# FlightComputer_DeploymentBoard.net
KiCad netlist of a schematic drawn in EAGLE
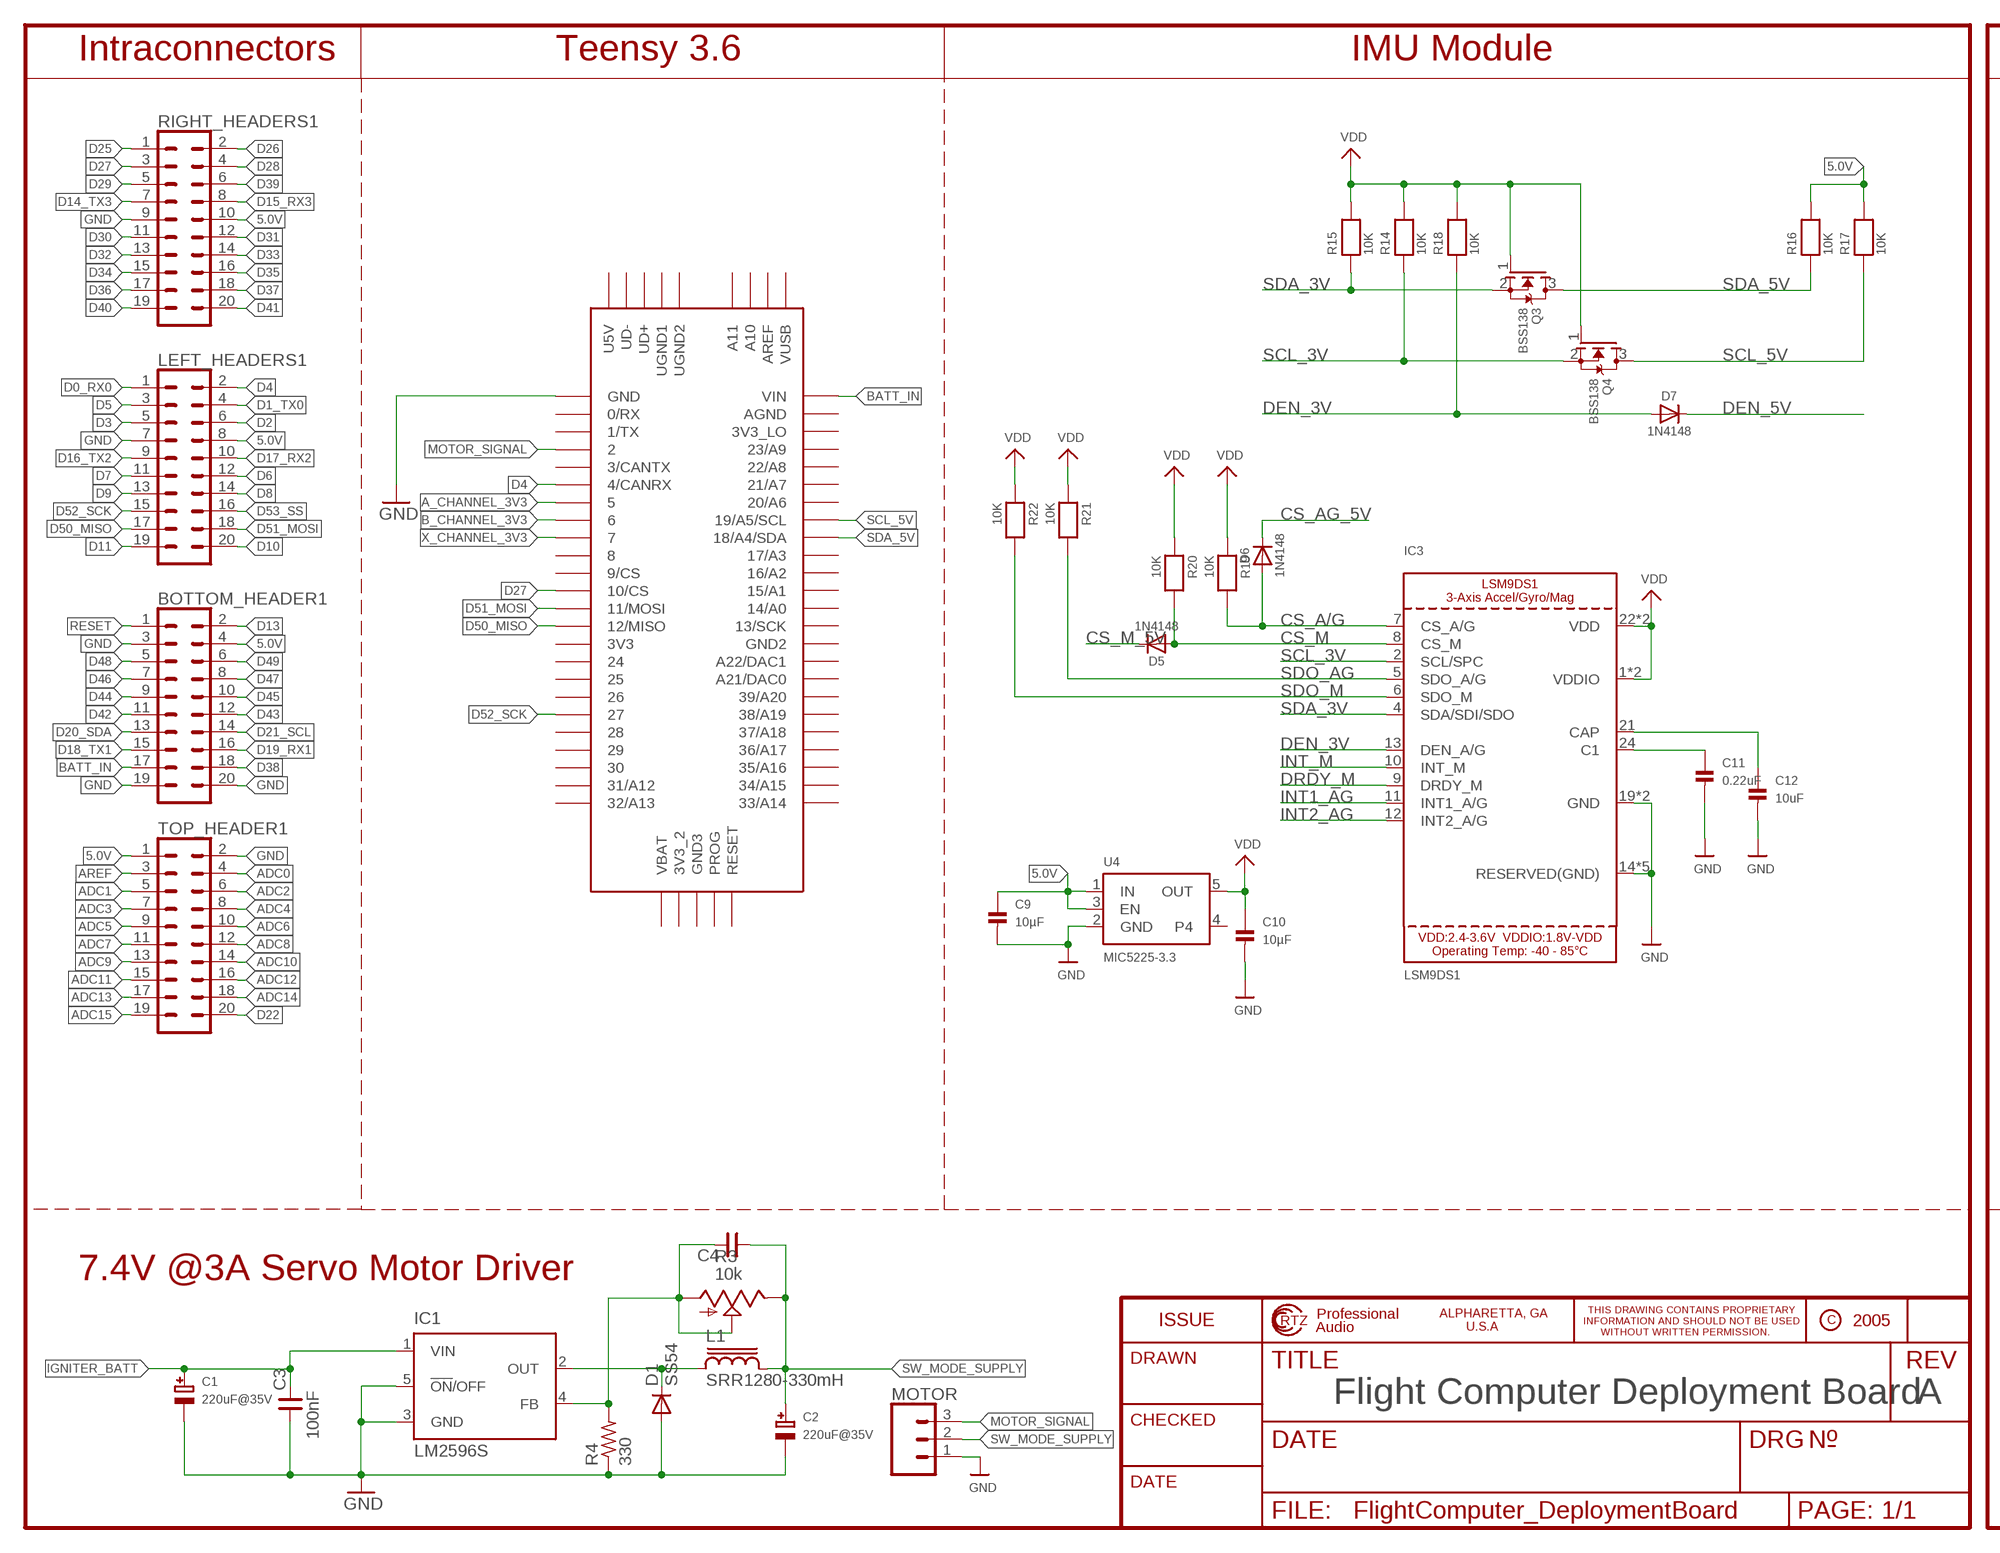
[diagram p0: schematic, sheet 1, part 1 of 2]
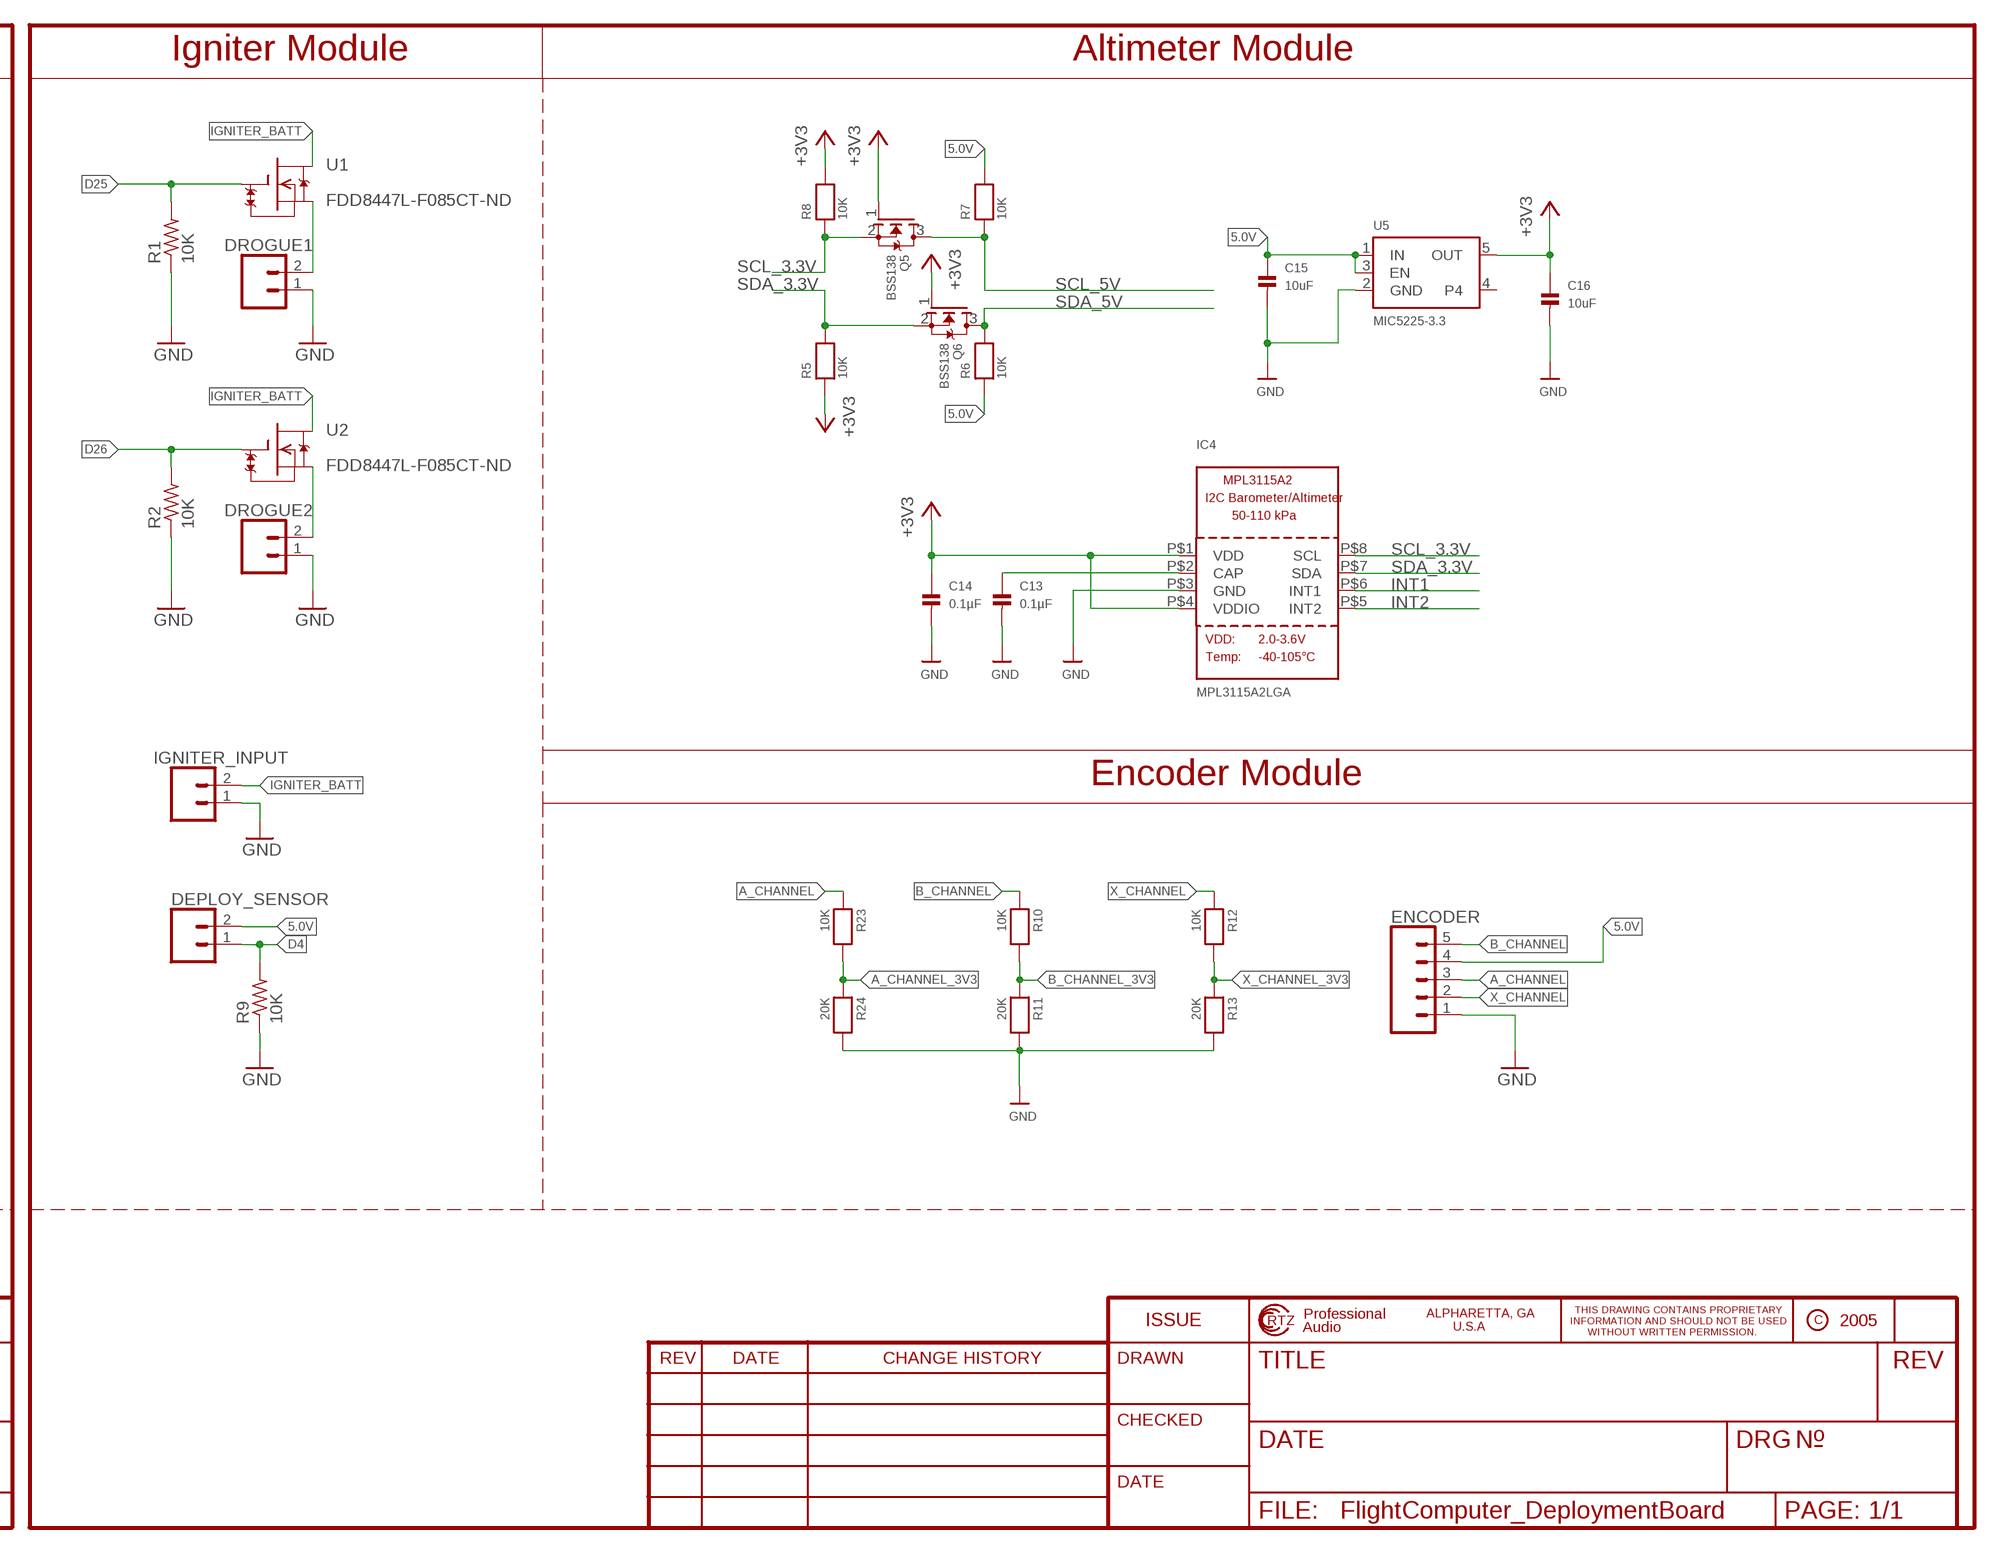
[diagram p1: schematic, sheet 1, part 2 of 2]

(export (version "E")
  (design (tool "Eeschema 10.0.6"))
  (components
    (comp (ref "BOTTOM_HEADER1")
      (value "CONN_10X2")
      (footprint "eagle-import:2X10")
      (libsource (lib "eagle-import") (part "CONN_10X2"))
    )
    (comp (ref "C1")
      (value "220uF@35V")
      (footprint "eagle-import:PANASONIC_D")
      (libsource (lib "eagle-import") (part "CAP_ELECTROLYTICPANASONIC_D"))
    )
    (comp (ref "C2")
      (value "220uF@35V")
      (footprint "eagle-import:PANASONIC_D")
      (libsource (lib "eagle-import") (part "CAP_ELECTROLYTICPANASONIC_D"))
    )
    (comp (ref "C3")
      (value "100nF")
      (footprint "eagle-import:0603")
      (libsource (lib "eagle-import") (part "CNP-0603"))
    )
    (comp (ref "C4")
      (value "CNP-0603")
      (footprint "eagle-import:0603")
      (libsource (lib "eagle-import") (part "CNP-0603"))
    )
    (comp (ref "C9")
      (value "10µF")
      (footprint "eagle-import:0603")
      (libsource (lib "eagle-import") (part "CAP_CERAMIC0603"))
    )
    (comp (ref "C10")
      (value "10µF")
      (footprint "eagle-import:0603")
      (libsource (lib "eagle-import") (part "CAP_CERAMIC0603"))
    )
    (comp (ref "C11")
      (value "0.22uF")
      (footprint "eagle-import:0603")
      (libsource (lib "eagle-import") (part "CAP_CERAMIC0603"))
    )
    (comp (ref "C12")
      (value "10uF")
      (footprint "eagle-import:0603")
      (libsource (lib "eagle-import") (part "CAP_CERAMIC0603"))
    )
    (comp (ref "C13")
      (value "0.1µF")
      (footprint "eagle-import:0603")
      (libsource (lib "eagle-import") (part "CAP_CERAMIC0603"))
    )
    (comp (ref "C14")
      (value "0.1µF")
      (footprint "eagle-import:0603")
      (libsource (lib "eagle-import") (part "CAP_CERAMIC0603"))
    )
    (comp (ref "C15")
      (value "10uF")
      (footprint "eagle-import:0603")
      (libsource (lib "eagle-import") (part "CAP_CERAMIC0603"))
    )
    (comp (ref "C16")
      (value "10uF")
      (footprint "eagle-import:0603")
      (libsource (lib "eagle-import") (part "CAP_CERAMIC0603"))
    )
    (comp (ref "D1")
      (value "SS54")
      (footprint "eagle-import:DO214AB")
      (fields (field (name "MF") "Fairchild") (field (name "MPN") "S3G"))
      (libsource (lib "eagle-import") (part "S3G"))
    )
    (comp (ref "D5")
      (value "1N4148")
      (footprint "eagle-import:SOD-323")
      (libsource (lib "eagle-import") (part "DIODESOD-323"))
    )
    (comp (ref "D6")
      (value "1N4148")
      (footprint "eagle-import:SOD-323")
      (libsource (lib "eagle-import") (part "DIODESOD-323"))
    )
    (comp (ref "D7")
      (value "1N4148")
      (footprint "eagle-import:SOD-323")
      (libsource (lib "eagle-import") (part "DIODESOD-323"))
    )
    (comp (ref "DEPLOY_SENSOR")
      (value "CONN_023.5MM")
      (footprint "eagle-import:SCREWTERMINAL-3.5MM-2")
      (libsource (lib "eagle-import") (part "CONN_023.5MM"))
    )
    (comp (ref "DROGUE1")
      (value "CONN_023.5MM")
      (footprint "eagle-import:SCREWTERMINAL-3.5MM-2")
      (libsource (lib "eagle-import") (part "CONN_023.5MM"))
    )
    (comp (ref "DROGUE2")
      (value "CONN_023.5MM")
      (footprint "eagle-import:SCREWTERMINAL-3.5MM-2")
      (libsource (lib "eagle-import") (part "CONN_023.5MM"))
    )
    (comp (ref "ENCODER")
      (value "CONN_05")
      (footprint "eagle-import:1X05")
      (libsource (lib "eagle-import") (part "CONN_05"))
    )
    (comp (ref "IC1")
      (value "LM2596S")
      (footprint "eagle-import:TO263-5")
      (fields (field (name "MF") "NATIONAL SEMICONDUCTOR") (field (name "MPN") "LM2596S-ADJ/NOPB"))
      (libsource (lib "eagle-import") (part "LM2596S"))
    )
    (comp (ref "IC3")
      (value "LSM9DS1")
      (footprint "eagle-import:LGA24_3.5X3.1MM")
      (libsource (lib "eagle-import") (part "LSM9DS1"))
    )
    (comp (ref "IC4")
      (value "MPL3115A2LGA")
      (footprint "eagle-import:LGA8")
      (libsource (lib "eagle-import") (part "MPL3115A2LGA"))
    )
    (comp (ref "IGNITER_INPUT")
      (value "CONN_02")
      (footprint "eagle-import:1X02")
      (libsource (lib "eagle-import") (part "CONN_02"))
    )
    (comp (ref "L1")
      (value "SRR1280-330mH")
      (footprint "eagle-import:SRR1280")
      (libsource (lib "eagle-import") (part "SRR1280"))
    )
    (comp (ref "LEFT_HEADERS1")
      (value "CONN_10X2")
      (footprint "eagle-import:2X10")
      (libsource (lib "eagle-import") (part "CONN_10X2"))
    )
    (comp (ref "MOTOR")
      (value "CONN_03")
      (footprint "eagle-import:1X03")
      (libsource (lib "eagle-import") (part "CONN_03"))
    )
    (comp (ref "Q3")
      (value "BSS138")
      (footprint "eagle-import:SOT23-WIDE")
      (libsource (lib "eagle-import") (part "MOSFET-NWIDE"))
    )
    (comp (ref "Q4")
      (value "BSS138")
      (footprint "eagle-import:SOT23-WIDE")
      (libsource (lib "eagle-import") (part "MOSFET-NWIDE"))
    )
    (comp (ref "Q5")
      (value "BSS138")
      (footprint "eagle-import:SOT23-WIDE")
      (libsource (lib "eagle-import") (part "MOSFET-NWIDE"))
    )
    (comp (ref "Q6")
      (value "BSS138")
      (footprint "eagle-import:SOT23-WIDE")
      (libsource (lib "eagle-import") (part "MOSFET-NWIDE"))
    )
    (comp (ref "R1")
      (value "10K")
      (footprint "eagle-import:R0805")
      (libsource (lib "eagle-import") (part "R-US_R0805"))
    )
    (comp (ref "R2")
      (value "10K")
      (footprint "eagle-import:R0805")
      (libsource (lib "eagle-import") (part "R-US_R0805"))
    )
    (comp (ref "R3")
      (value "10k")
      (footprint "eagle-import:S64W")
      (libsource (lib "eagle-import") (part "TRIM_US-S64W"))
    )
    (comp (ref "R4")
      (value "330")
      (footprint "eagle-import:R0603")
      (libsource (lib "eagle-import") (part "R-US_R0603"))
    )
    (comp (ref "R5")
      (value "10K")
      (footprint "eagle-import:0603")
      (libsource (lib "eagle-import") (part "RESISTOR0603"))
    )
    (comp (ref "R6")
      (value "10K")
      (footprint "eagle-import:0603")
      (libsource (lib "eagle-import") (part "RESISTOR0603"))
    )
    (comp (ref "R7")
      (value "10K")
      (footprint "eagle-import:0603")
      (libsource (lib "eagle-import") (part "RESISTOR0603"))
    )
    (comp (ref "R8")
      (value "10K")
      (footprint "eagle-import:0603")
      (libsource (lib "eagle-import") (part "RESISTOR0603"))
    )
    (comp (ref "R9")
      (value "10K")
      (footprint "eagle-import:R0805")
      (libsource (lib "eagle-import") (part "R-US_R0805"))
    )
    (comp (ref "R10")
      (value "10K")
      (footprint "eagle-import:0603")
      (libsource (lib "eagle-import") (part "RESISTOR0603"))
    )
    (comp (ref "R11")
      (value "20K")
      (footprint "eagle-import:0603")
      (libsource (lib "eagle-import") (part "RESISTOR0603"))
    )
    (comp (ref "R12")
      (value "10K")
      (footprint "eagle-import:0603")
      (libsource (lib "eagle-import") (part "RESISTOR0603"))
    )
    (comp (ref "R13")
      (value "20K")
      (footprint "eagle-import:0603")
      (libsource (lib "eagle-import") (part "RESISTOR0603"))
    )
    (comp (ref "R14")
      (value "10K")
      (footprint "eagle-import:0603")
      (libsource (lib "eagle-import") (part "RESISTOR0603"))
    )
    (comp (ref "R15")
      (value "10K")
      (footprint "eagle-import:0603")
      (libsource (lib "eagle-import") (part "RESISTOR0603"))
    )
    (comp (ref "R16")
      (value "10K")
      (footprint "eagle-import:0603")
      (libsource (lib "eagle-import") (part "RESISTOR0603"))
    )
    (comp (ref "R17")
      (value "10K")
      (footprint "eagle-import:0603")
      (libsource (lib "eagle-import") (part "RESISTOR0603"))
    )
    (comp (ref "R18")
      (value "10K")
      (footprint "eagle-import:0603")
      (libsource (lib "eagle-import") (part "RESISTOR0603"))
    )
    (comp (ref "R19")
      (value "10K")
      (footprint "eagle-import:0603")
      (libsource (lib "eagle-import") (part "RESISTOR0603"))
    )
    (comp (ref "R20")
      (value "10K")
      (footprint "eagle-import:0603")
      (libsource (lib "eagle-import") (part "RESISTOR0603"))
    )
    (comp (ref "R21")
      (value "10K")
      (footprint "eagle-import:0603")
      (libsource (lib "eagle-import") (part "RESISTOR0603"))
    )
    (comp (ref "R22")
      (value "10K")
      (footprint "eagle-import:0603")
      (libsource (lib "eagle-import") (part "RESISTOR0603"))
    )
    (comp (ref "R23")
      (value "10K")
      (footprint "eagle-import:0603")
      (libsource (lib "eagle-import") (part "RESISTOR0603"))
    )
    (comp (ref "R24")
      (value "20K")
      (footprint "eagle-import:0603")
      (libsource (lib "eagle-import") (part "RESISTOR0603"))
    )
    (comp (ref "RIGHT_HEADERS1")
      (value "CONN_10X2")
      (footprint "eagle-import:2X10")
      (libsource (lib "eagle-import") (part "CONN_10X2"))
    )
    (comp (ref "TOP_HEADER1")
      (value "CONN_10X2")
      (footprint "eagle-import:2X10")
      (libsource (lib "eagle-import") (part "CONN_10X2"))
    )
    (comp (ref "U$1")
      (value "TEENSY_3.5/3.6")
      (footprint "eagle-import:TEENSY_3.5_3.6")
      (libsource (lib "eagle-import") (part "TEENSY_3.5/3.6"))
    )
    (comp (ref "U1")
      (value "FDD8447L-F085CT-ND")
      (footprint "eagle-import:TO252")
      (libsource (lib "eagle-import") (part "TSM4ND50"))
    )
    (comp (ref "U2")
      (value "FDD8447L-F085CT-ND")
      (footprint "eagle-import:TO252")
      (libsource (lib "eagle-import") (part "TSM4ND50"))
    )
    (comp (ref "U4")
      (value "MIC5225-3.3")
      (footprint "eagle-import:SOT23-5")
      (libsource (lib "eagle-import") (part "VREG_SOT23-5"))
    )
    (comp (ref "U5")
      (value "MIC5225-3.3")
      (footprint "eagle-import:SOT23-5")
      (libsource (lib "eagle-import") (part "VREG_SOT23-5"))
    )
  )
  (nets
    (net (code "1") (name "+3V3") (class "Default")
      (node (ref "C14") (pin "1") (pinfunction "P$1_1") (pintype "passive"))
      (node (ref "C16") (pin "1") (pinfunction "P$1_1") (pintype "passive"))
      (node (ref "IC4") (pin "P$1") (pinfunction "VDD_P$1") (pintype "power_in"))
      (node (ref "IC4") (pin "P$4") (pinfunction "VDDIO_P$4") (pintype "power_in"))
      (node (ref "Q5") (pin "1") (pinfunction "G_1") (pintype "bidirectional"))
      (node (ref "Q6") (pin "1") (pinfunction "G_1") (pintype "bidirectional"))
      (node (ref "R5") (pin "1") (pinfunction "1_1") (pintype "passive"))
      (node (ref "R8") (pin "2") (pinfunction "2_2") (pintype "passive"))
      (node (ref "U5") (pin "5") (pinfunction "OUT_5") (pintype "power_in"))
    )
    (net (code "2") (name "/CS_AG_5V") (class "Default")
      (node (ref "D6") (pin "C") (pinfunction "C_C") (pintype "passive"))
    )
    (net (code "3") (name "/CS_A{slash}G") (class "Default")
      (node (ref "D6") (pin "A") (pinfunction "A_A") (pintype "passive"))
      (node (ref "IC3") (pin "7") (pinfunction "CS_A/G_7") (pintype "bidirectional"))
      (node (ref "R19") (pin "2") (pinfunction "2_2") (pintype "passive"))
    )
    (net (code "4") (name "/CS_M") (class "Default")
      (node (ref "D5") (pin "A") (pinfunction "A_A") (pintype "passive"))
      (node (ref "IC3") (pin "8") (pinfunction "CS_M_8") (pintype "bidirectional"))
      (node (ref "R20") (pin "2") (pinfunction "2_2") (pintype "passive"))
    )
    (net (code "5") (name "/CS_M_5V") (class "Default")
      (node (ref "D5") (pin "C") (pinfunction "C_C") (pintype "passive"))
    )
    (net (code "6") (name "/DEN_3V") (class "Default")
      (node (ref "D7") (pin "A") (pinfunction "A_A") (pintype "passive"))
      (node (ref "IC3") (pin "13") (pinfunction "DEN_A/G_13") (pintype "bidirectional"))
      (node (ref "R18") (pin "1") (pinfunction "1_1") (pintype "passive"))
    )
    (net (code "7") (name "/DEN_5V") (class "Default")
      (node (ref "D7") (pin "C") (pinfunction "C_C") (pintype "passive"))
    )
    (net (code "8") (name "/DRDY_M") (class "Default")
      (node (ref "IC3") (pin "9") (pinfunction "DRDY_M_9") (pintype "bidirectional"))
    )
    (net (code "9") (name "/INT1") (class "Default")
      (node (ref "IC4") (pin "P$6") (pinfunction "INT1_P$6") (pintype "output"))
    )
    (net (code "10") (name "/INT1_AG") (class "Default")
      (node (ref "IC3") (pin "11") (pinfunction "INT1_A/G_11") (pintype "bidirectional"))
    )
    (net (code "11") (name "/INT2") (class "Default")
      (node (ref "IC4") (pin "P$5") (pinfunction "INT2_P$5") (pintype "output"))
    )
    (net (code "12") (name "/INT2_AG") (class "Default")
      (node (ref "IC3") (pin "12") (pinfunction "INT2_A/G_12") (pintype "bidirectional"))
    )
    (net (code "13") (name "/INT_M") (class "Default")
      (node (ref "IC3") (pin "10") (pinfunction "INT_M_10") (pintype "bidirectional"))
    )
    (net (code "14") (name "/SCL_3.3V") (class "Default")
      (node (ref "IC4") (pin "P$8") (pinfunction "SCL_P$8") (pintype "bidirectional"))
      (node (ref "Q5") (pin "2") (pinfunction "S_2") (pintype "bidirectional"))
      (node (ref "R8") (pin "1") (pinfunction "1_1") (pintype "passive"))
    )
    (net (code "15") (name "/SCL_3V") (class "Default")
      (node (ref "IC3") (pin "2") (pinfunction "SCL/SPC_2") (pintype "bidirectional"))
      (node (ref "Q4") (pin "2") (pinfunction "S_2") (pintype "bidirectional"))
      (node (ref "R14") (pin "1") (pinfunction "1_1") (pintype "passive"))
    )
    (net (code "16") (name "/SDA_3.3V") (class "Default")
      (node (ref "IC4") (pin "P$7") (pinfunction "SDA_P$7") (pintype "bidirectional"))
      (node (ref "Q6") (pin "2") (pinfunction "S_2") (pintype "bidirectional"))
      (node (ref "R5") (pin "2") (pinfunction "2_2") (pintype "passive"))
    )
    (net (code "17") (name "/SDA_3V") (class "Default")
      (node (ref "IC3") (pin "4") (pinfunction "SDA/SDI/SDO_4") (pintype "bidirectional"))
      (node (ref "Q3") (pin "2") (pinfunction "S_2") (pintype "bidirectional"))
      (node (ref "R15") (pin "1") (pinfunction "1_1") (pintype "passive"))
    )
    (net (code "18") (name "/SDO_AG") (class "Default")
      (node (ref "IC3") (pin "5") (pinfunction "SDO_A/G_5") (pintype "bidirectional"))
      (node (ref "R21") (pin "2") (pinfunction "2_2") (pintype "passive"))
    )
    (net (code "19") (name "/SDO_M") (class "Default")
      (node (ref "IC3") (pin "6") (pinfunction "SDO_M_6") (pintype "bidirectional"))
      (node (ref "R22") (pin "2") (pinfunction "2_2") (pintype "passive"))
    )
    (net (code "20") (name "5.0V") (class "Default")
      (node (ref "BOTTOM_HEADER1") (pin "4") (pinfunction "4_4") (pintype "passive"))
      (node (ref "C15") (pin "1") (pinfunction "P$1_1") (pintype "passive"))
      (node (ref "C9") (pin "1") (pinfunction "P$1_1") (pintype "passive"))
      (node (ref "DEPLOY_SENSOR") (pin "2") (pinfunction "2_2") (pintype "passive"))
      (node (ref "ENCODER") (pin "4") (pinfunction "4_4") (pintype "passive"))
      (node (ref "LEFT_HEADERS1") (pin "8") (pinfunction "8_8") (pintype "passive"))
      (node (ref "R16") (pin "2") (pinfunction "2_2") (pintype "passive"))
      (node (ref "R17") (pin "2") (pinfunction "2_2") (pintype "passive"))
      (node (ref "R6") (pin "1") (pinfunction "1_1") (pintype "passive"))
      (node (ref "R7") (pin "2") (pinfunction "2_2") (pintype "passive"))
      (node (ref "RIGHT_HEADERS1") (pin "10") (pinfunction "10_10") (pintype "passive"))
      (node (ref "TOP_HEADER1") (pin "1") (pinfunction "1_1") (pintype "passive"))
      (node (ref "U4") (pin "1") (pinfunction "IN_1") (pintype "power_in"))
      (node (ref "U4") (pin "3") (pinfunction "EN_3") (pintype "input"))
      (node (ref "U5") (pin "1") (pinfunction "IN_1") (pintype "power_in"))
      (node (ref "U5") (pin "3") (pinfunction "EN_3") (pintype "input"))
    )
    (net (code "21") (name "ADC0") (class "Default")
      (node (ref "TOP_HEADER1") (pin "4") (pinfunction "4_4") (pintype "passive"))
    )
    (net (code "22") (name "ADC1") (class "Default")
      (node (ref "TOP_HEADER1") (pin "5") (pinfunction "5_5") (pintype "passive"))
    )
    (net (code "23") (name "ADC2") (class "Default")
      (node (ref "TOP_HEADER1") (pin "6") (pinfunction "6_6") (pintype "passive"))
    )
    (net (code "24") (name "ADC3") (class "Default")
      (node (ref "TOP_HEADER1") (pin "7") (pinfunction "7_7") (pintype "passive"))
    )
    (net (code "25") (name "ADC4") (class "Default")
      (node (ref "TOP_HEADER1") (pin "8") (pinfunction "8_8") (pintype "passive"))
    )
    (net (code "26") (name "ADC5") (class "Default")
      (node (ref "TOP_HEADER1") (pin "9") (pinfunction "9_9") (pintype "passive"))
    )
    (net (code "27") (name "ADC6") (class "Default")
      (node (ref "TOP_HEADER1") (pin "10") (pinfunction "10_10") (pintype "passive"))
    )
    (net (code "28") (name "ADC7") (class "Default")
      (node (ref "TOP_HEADER1") (pin "11") (pinfunction "11_11") (pintype "passive"))
    )
    (net (code "29") (name "ADC8") (class "Default")
      (node (ref "TOP_HEADER1") (pin "12") (pinfunction "12_12") (pintype "passive"))
    )
    (net (code "30") (name "ADC9") (class "Default")
      (node (ref "TOP_HEADER1") (pin "13") (pinfunction "13_13") (pintype "passive"))
    )
    (net (code "31") (name "ADC10") (class "Default")
      (node (ref "TOP_HEADER1") (pin "14") (pinfunction "14_14") (pintype "passive"))
    )
    (net (code "32") (name "ADC11") (class "Default")
      (node (ref "TOP_HEADER1") (pin "15") (pinfunction "15_15") (pintype "passive"))
    )
    (net (code "33") (name "ADC12") (class "Default")
      (node (ref "TOP_HEADER1") (pin "16") (pinfunction "16_16") (pintype "passive"))
    )
    (net (code "34") (name "ADC13") (class "Default")
      (node (ref "TOP_HEADER1") (pin "17") (pinfunction "17_17") (pintype "passive"))
    )
    (net (code "35") (name "ADC14") (class "Default")
      (node (ref "TOP_HEADER1") (pin "18") (pinfunction "18_18") (pintype "passive"))
    )
    (net (code "36") (name "ADC15") (class "Default")
      (node (ref "TOP_HEADER1") (pin "19") (pinfunction "19_19") (pintype "passive"))
    )
    (net (code "37") (name "AREF") (class "Default")
      (node (ref "TOP_HEADER1") (pin "3") (pinfunction "3_3") (pintype "passive"))
    )
    (net (code "38") (name "A_CHANNEL") (class "Default")
      (node (ref "ENCODER") (pin "3") (pinfunction "3_3") (pintype "passive"))
      (node (ref "R23") (pin "1") (pinfunction "1_1") (pintype "passive"))
    )
    (net (code "39") (name "A_CHANNEL_3V3") (class "Default")
      (node (ref "R23") (pin "2") (pinfunction "2_2") (pintype "passive"))
      (node (ref "R24") (pin "1") (pinfunction "1_1") (pintype "passive"))
      (node (ref "U$1") (pin "5") (pinfunction "5_5") (pintype "bidirectional"))
    )
    (net (code "40") (name "BATT_IN") (class "Default")
      (node (ref "BOTTOM_HEADER1") (pin "17") (pinfunction "17_17") (pintype "passive"))
      (node (ref "U$1") (pin "VIN") (pinfunction "VIN_VIN") (pintype "bidirectional"))
    )
    (net (code "41") (name "B_CHANNEL") (class "Default")
      (node (ref "ENCODER") (pin "5") (pinfunction "5_5") (pintype "passive"))
      (node (ref "R10") (pin "1") (pinfunction "1_1") (pintype "passive"))
    )
    (net (code "42") (name "B_CHANNEL_3V3") (class "Default")
      (node (ref "R10") (pin "2") (pinfunction "2_2") (pintype "passive"))
      (node (ref "R11") (pin "1") (pinfunction "1_1") (pintype "passive"))
      (node (ref "U$1") (pin "6") (pinfunction "6_6") (pintype "bidirectional"))
    )
    (net (code "43") (name "D0_RX0") (class "Default")
      (node (ref "LEFT_HEADERS1") (pin "1") (pinfunction "1_1") (pintype "passive"))
    )
    (net (code "44") (name "D1_TX0") (class "Default")
      (node (ref "LEFT_HEADERS1") (pin "4") (pinfunction "4_4") (pintype "passive"))
    )
    (net (code "45") (name "D2") (class "Default")
      (node (ref "LEFT_HEADERS1") (pin "6") (pinfunction "6_6") (pintype "passive"))
    )
    (net (code "46") (name "D3") (class "Default")
      (node (ref "LEFT_HEADERS1") (pin "5") (pinfunction "5_5") (pintype "passive"))
    )
    (net (code "47") (name "D4") (class "Default")
      (node (ref "DEPLOY_SENSOR") (pin "1") (pinfunction "1_1") (pintype "passive"))
      (node (ref "LEFT_HEADERS1") (pin "2") (pinfunction "2_2") (pintype "passive"))
      (node (ref "R9") (pin "2") (pinfunction "2_2") (pintype "passive"))
      (node (ref "U$1") (pin "4/CANRX") (pinfunction "4/CANRX_4/CANRX") (pintype "bidirectional"))
    )
    (net (code "48") (name "D5") (class "Default")
      (node (ref "LEFT_HEADERS1") (pin "3") (pinfunction "3_3") (pintype "passive"))
    )
    (net (code "49") (name "D6") (class "Default")
      (node (ref "LEFT_HEADERS1") (pin "12") (pinfunction "12_12") (pintype "passive"))
    )
    (net (code "50") (name "D7") (class "Default")
      (node (ref "LEFT_HEADERS1") (pin "11") (pinfunction "11_11") (pintype "passive"))
    )
    (net (code "51") (name "D8") (class "Default")
      (node (ref "LEFT_HEADERS1") (pin "14") (pinfunction "14_14") (pintype "passive"))
    )
    (net (code "52") (name "D9") (class "Default")
      (node (ref "LEFT_HEADERS1") (pin "13") (pinfunction "13_13") (pintype "passive"))
    )
    (net (code "53") (name "D10") (class "Default")
      (node (ref "LEFT_HEADERS1") (pin "20") (pinfunction "20_20") (pintype "passive"))
    )
    (net (code "54") (name "D11") (class "Default")
      (node (ref "LEFT_HEADERS1") (pin "19") (pinfunction "19_19") (pintype "passive"))
    )
    (net (code "55") (name "D13") (class "Default")
      (node (ref "BOTTOM_HEADER1") (pin "2") (pinfunction "2_2") (pintype "passive"))
    )
    (net (code "56") (name "D14_TX3") (class "Default")
      (node (ref "RIGHT_HEADERS1") (pin "7") (pinfunction "7_7") (pintype "passive"))
    )
    (net (code "57") (name "D15_RX3") (class "Default")
      (node (ref "RIGHT_HEADERS1") (pin "8") (pinfunction "8_8") (pintype "passive"))
    )
    (net (code "58") (name "D16_TX2") (class "Default")
      (node (ref "LEFT_HEADERS1") (pin "9") (pinfunction "9_9") (pintype "passive"))
    )
    (net (code "59") (name "D17_RX2") (class "Default")
      (node (ref "LEFT_HEADERS1") (pin "10") (pinfunction "10_10") (pintype "passive"))
    )
    (net (code "60") (name "D18_TX1") (class "Default")
      (node (ref "BOTTOM_HEADER1") (pin "15") (pinfunction "15_15") (pintype "passive"))
    )
    (net (code "61") (name "D19_RX1") (class "Default")
      (node (ref "BOTTOM_HEADER1") (pin "16") (pinfunction "16_16") (pintype "passive"))
    )
    (net (code "62") (name "D20_SDA") (class "Default")
      (node (ref "BOTTOM_HEADER1") (pin "13") (pinfunction "13_13") (pintype "passive"))
    )
    (net (code "63") (name "D21_SCL") (class "Default")
      (node (ref "BOTTOM_HEADER1") (pin "14") (pinfunction "14_14") (pintype "passive"))
    )
    (net (code "64") (name "D22") (class "Default")
      (node (ref "TOP_HEADER1") (pin "20") (pinfunction "20_20") (pintype "passive"))
    )
    (net (code "65") (name "D25") (class "Default")
      (node (ref "R1") (pin "2") (pinfunction "2_2") (pintype "passive"))
      (node (ref "RIGHT_HEADERS1") (pin "1") (pinfunction "1_1") (pintype "passive"))
      (node (ref "U1") (pin "G") (pinfunction "G_G") (pintype "passive"))
    )
    (net (code "66") (name "D26") (class "Default")
      (node (ref "R2") (pin "2") (pinfunction "2_2") (pintype "passive"))
      (node (ref "RIGHT_HEADERS1") (pin "2") (pinfunction "2_2") (pintype "passive"))
      (node (ref "U2") (pin "G") (pinfunction "G_G") (pintype "passive"))
    )
    (net (code "67") (name "D27") (class "Default")
      (node (ref "RIGHT_HEADERS1") (pin "3") (pinfunction "3_3") (pintype "passive"))
      (node (ref "U$1") (pin "10/CS") (pinfunction "10/CS_10/CS") (pintype "bidirectional"))
    )
    (net (code "68") (name "D28") (class "Default")
      (node (ref "RIGHT_HEADERS1") (pin "4") (pinfunction "4_4") (pintype "passive"))
    )
    (net (code "69") (name "D29") (class "Default")
      (node (ref "RIGHT_HEADERS1") (pin "5") (pinfunction "5_5") (pintype "passive"))
    )
    (net (code "70") (name "D30") (class "Default")
      (node (ref "RIGHT_HEADERS1") (pin "11") (pinfunction "11_11") (pintype "passive"))
    )
    (net (code "71") (name "D31") (class "Default")
      (node (ref "RIGHT_HEADERS1") (pin "12") (pinfunction "12_12") (pintype "passive"))
    )
    (net (code "72") (name "D32") (class "Default")
      (node (ref "RIGHT_HEADERS1") (pin "13") (pinfunction "13_13") (pintype "passive"))
    )
    (net (code "73") (name "D33") (class "Default")
      (node (ref "RIGHT_HEADERS1") (pin "14") (pinfunction "14_14") (pintype "passive"))
    )
    (net (code "74") (name "D34") (class "Default")
      (node (ref "RIGHT_HEADERS1") (pin "15") (pinfunction "15_15") (pintype "passive"))
    )
    (net (code "75") (name "D35") (class "Default")
      (node (ref "RIGHT_HEADERS1") (pin "16") (pinfunction "16_16") (pintype "passive"))
    )
    (net (code "76") (name "D36") (class "Default")
      (node (ref "RIGHT_HEADERS1") (pin "17") (pinfunction "17_17") (pintype "passive"))
    )
    (net (code "77") (name "D37") (class "Default")
      (node (ref "RIGHT_HEADERS1") (pin "18") (pinfunction "18_18") (pintype "passive"))
    )
    (net (code "78") (name "D38") (class "Default")
      (node (ref "BOTTOM_HEADER1") (pin "18") (pinfunction "18_18") (pintype "passive"))
    )
    (net (code "79") (name "D39") (class "Default")
      (node (ref "RIGHT_HEADERS1") (pin "6") (pinfunction "6_6") (pintype "passive"))
    )
    (net (code "80") (name "D40") (class "Default")
      (node (ref "RIGHT_HEADERS1") (pin "19") (pinfunction "19_19") (pintype "passive"))
    )
    (net (code "81") (name "D41") (class "Default")
      (node (ref "RIGHT_HEADERS1") (pin "20") (pinfunction "20_20") (pintype "passive"))
    )
    (net (code "82") (name "D42") (class "Default")
      (node (ref "BOTTOM_HEADER1") (pin "11") (pinfunction "11_11") (pintype "passive"))
    )
    (net (code "83") (name "D43") (class "Default")
      (node (ref "BOTTOM_HEADER1") (pin "12") (pinfunction "12_12") (pintype "passive"))
    )
    (net (code "84") (name "D44") (class "Default")
      (node (ref "BOTTOM_HEADER1") (pin "9") (pinfunction "9_9") (pintype "passive"))
    )
    (net (code "85") (name "D45") (class "Default")
      (node (ref "BOTTOM_HEADER1") (pin "10") (pinfunction "10_10") (pintype "passive"))
    )
    (net (code "86") (name "D46") (class "Default")
      (node (ref "BOTTOM_HEADER1") (pin "7") (pinfunction "7_7") (pintype "passive"))
    )
    (net (code "87") (name "D47") (class "Default")
      (node (ref "BOTTOM_HEADER1") (pin "8") (pinfunction "8_8") (pintype "passive"))
    )
    (net (code "88") (name "D48") (class "Default")
      (node (ref "BOTTOM_HEADER1") (pin "5") (pinfunction "5_5") (pintype "passive"))
    )
    (net (code "89") (name "D49") (class "Default")
      (node (ref "BOTTOM_HEADER1") (pin "6") (pinfunction "6_6") (pintype "passive"))
    )
    (net (code "90") (name "D50_MISO") (class "Default")
      (node (ref "LEFT_HEADERS1") (pin "17") (pinfunction "17_17") (pintype "passive"))
      (node (ref "U$1") (pin "12/MISO") (pinfunction "12/MISO_12/MISO") (pintype "bidirectional"))
    )
    (net (code "91") (name "D51_MOSI") (class "Default")
      (node (ref "LEFT_HEADERS1") (pin "18") (pinfunction "18_18") (pintype "passive"))
      (node (ref "U$1") (pin "11/MOSI") (pinfunction "11/MOSI_11/MOSI") (pintype "bidirectional"))
    )
    (net (code "92") (name "D52_SCK") (class "Default")
      (node (ref "LEFT_HEADERS1") (pin "15") (pinfunction "15_15") (pintype "passive"))
      (node (ref "U$1") (pin "27") (pinfunction "27_27") (pintype "bidirectional"))
    )
    (net (code "93") (name "D53_SS") (class "Default")
      (node (ref "LEFT_HEADERS1") (pin "16") (pinfunction "16_16") (pintype "passive"))
    )
    (net (code "94") (name "GND") (class "Default")
      (node (ref "BOTTOM_HEADER1") (pin "19") (pinfunction "19_19") (pintype "passive"))
      (node (ref "BOTTOM_HEADER1") (pin "20") (pinfunction "20_20") (pintype "passive"))
      (node (ref "BOTTOM_HEADER1") (pin "3") (pinfunction "3_3") (pintype "passive"))
      (node (ref "C1") (pin "-") (pinfunction "-_-") (pintype "passive"))
      (node (ref "C10") (pin "2") (pinfunction "P$2_2") (pintype "passive"))
      (node (ref "C11") (pin "2") (pinfunction "P$2_2") (pintype "passive"))
      (node (ref "C12") (pin "2") (pinfunction "P$2_2") (pintype "passive"))
      (node (ref "C13") (pin "2") (pinfunction "P$2_2") (pintype "passive"))
      (node (ref "C14") (pin "2") (pinfunction "P$2_2") (pintype "passive"))
      (node (ref "C15") (pin "2") (pinfunction "P$2_2") (pintype "passive"))
      (node (ref "C16") (pin "2") (pinfunction "P$2_2") (pintype "passive"))
      (node (ref "C2") (pin "-") (pinfunction "-_-") (pintype "passive"))
      (node (ref "C3") (pin "1") (pinfunction "1_1") (pintype "passive"))
      (node (ref "C9") (pin "2") (pinfunction "P$2_2") (pintype "passive"))
      (node (ref "D1") (pin "A") (pinfunction "A_A") (pintype "passive"))
      (node (ref "DROGUE1") (pin "1") (pinfunction "1_1") (pintype "passive"))
      (node (ref "DROGUE2") (pin "1") (pinfunction "1_1") (pintype "passive"))
      (node (ref "ENCODER") (pin "1") (pinfunction "1_1") (pintype "passive"))
      (node (ref "IC1") (pin "3") (pinfunction "GND_3") (pintype "power_in"))
      (node (ref "IC1") (pin "5") (pinfunction "~{ON}/OFF_5") (pintype "input"))
      (node (ref "IC3") (pin "14") (pinfunction "RESERVED(GND)_14") (pintype "power_in"))
      (node (ref "IC3") (pin "15") (pinfunction "RESERVED(GND)_15") (pintype "power_in"))
      (node (ref "IC3") (pin "16") (pinfunction "RESERVED(GND)_16") (pintype "power_in"))
      (node (ref "IC3") (pin "17") (pinfunction "RESERVED(GND)_17") (pintype "power_in"))
      (node (ref "IC3") (pin "18") (pinfunction "RESERVED(GND)_18") (pintype "power_in"))
      (node (ref "IC3") (pin "19") (pinfunction "GND_19") (pintype "power_in"))
      (node (ref "IC3") (pin "20") (pinfunction "GND_20") (pintype "power_in"))
      (node (ref "IC4") (pin "P$3") (pinfunction "GND_P$3") (pintype "power_in"))
      (node (ref "IGNITER_INPUT") (pin "1") (pinfunction "1_1") (pintype "passive"))
      (node (ref "LEFT_HEADERS1") (pin "7") (pinfunction "7_7") (pintype "passive"))
      (node (ref "MOTOR") (pin "1") (pinfunction "1_1") (pintype "passive"))
      (node (ref "R1") (pin "1") (pinfunction "1_1") (pintype "passive"))
      (node (ref "R11") (pin "2") (pinfunction "2_2") (pintype "passive"))
      (node (ref "R13") (pin "2") (pinfunction "2_2") (pintype "passive"))
      (node (ref "R2") (pin "1") (pinfunction "1_1") (pintype "passive"))
      (node (ref "R24") (pin "2") (pinfunction "2_2") (pintype "passive"))
      (node (ref "R4") (pin "1") (pinfunction "1_1") (pintype "passive"))
      (node (ref "R9") (pin "1") (pinfunction "1_1") (pintype "passive"))
      (node (ref "RIGHT_HEADERS1") (pin "9") (pinfunction "9_9") (pintype "passive"))
      (node (ref "TOP_HEADER1") (pin "2") (pinfunction "2_2") (pintype "passive"))
      (node (ref "U$1") (pin "GND") (pinfunction "GND_GND") (pintype "bidirectional"))
      (node (ref "U4") (pin "2") (pinfunction "GND_2") (pintype "power_in"))
      (node (ref "U5") (pin "2") (pinfunction "GND_2") (pintype "power_in"))
    )
    (net (code "95") (name "IGNITER_BATT") (class "Default")
      (node (ref "C1") (pin "+") (pinfunction "+_+") (pintype "passive"))
      (node (ref "C3") (pin "2") (pinfunction "2_2") (pintype "passive"))
      (node (ref "IC1") (pin "1") (pinfunction "VIN_1") (pintype "input"))
      (node (ref "IGNITER_INPUT") (pin "2") (pinfunction "2_2") (pintype "passive"))
      (node (ref "U1") (pin "D") (pinfunction "D_D") (pintype "passive"))
      (node (ref "U2") (pin "D") (pinfunction "D_D") (pintype "passive"))
    )
    (net (code "96") (name "MOTOR_SIGNAL") (class "Default")
      (node (ref "MOTOR") (pin "3") (pinfunction "3_3") (pintype "passive"))
      (node (ref "U$1") (pin "2") (pinfunction "2_2") (pintype "bidirectional"))
    )
    (net (code "97") (name "Net-(C11-P$1)") (class "Default")
      (node (ref "C11") (pin "1") (pinfunction "P$1_1") (pintype "passive"))
      (node (ref "IC3") (pin "24") (pinfunction "C1_24") (pintype "bidirectional"))
    )
    (net (code "98") (name "Net-(C12-P$1)") (class "Default")
      (node (ref "C12") (pin "1") (pinfunction "P$1_1") (pintype "passive"))
      (node (ref "IC3") (pin "21") (pinfunction "CAP_21") (pintype "bidirectional"))
    )
    (net (code "99") (name "Net-(C13-P$1)") (class "Default")
      (node (ref "C13") (pin "1") (pinfunction "P$1_1") (pintype "passive"))
      (node (ref "IC4") (pin "P$2") (pinfunction "CAP_P$2") (pintype "passive"))
    )
    (net (code "100") (name "Net-(DROGUE1-Pad2)") (class "Default")
      (node (ref "DROGUE1") (pin "2") (pinfunction "2_2") (pintype "passive"))
      (node (ref "U1") (pin "S") (pinfunction "S_S") (pintype "passive"))
    )
    (net (code "101") (name "Net-(DROGUE2-Pad2)") (class "Default")
      (node (ref "DROGUE2") (pin "2") (pinfunction "2_2") (pintype "passive"))
      (node (ref "U2") (pin "S") (pinfunction "S_S") (pintype "passive"))
    )
    (net (code "102") (name "Net-(IC1-FB)") (class "Default")
      (node (ref "C4") (pin "2") (pinfunction "2_2") (pintype "passive"))
      (node (ref "IC1") (pin "4") (pinfunction "FB_4") (pintype "input"))
      (node (ref "R3") (pin "A") (pinfunction "A_A") (pintype "passive"))
      (node (ref "R3") (pin "S") (pinfunction "S_S") (pintype "passive"))
      (node (ref "R4") (pin "2") (pinfunction "2_2") (pintype "passive"))
    )
    (net (code "103") (name "Net-(IC1-OUT)") (class "Default")
      (node (ref "D1") (pin "C") (pinfunction "C_C") (pintype "passive"))
      (node (ref "IC1") (pin "2") (pinfunction "OUT_2") (pintype "output"))
      (node (ref "L1") (pin "1") (pinfunction "1_1") (pintype "passive"))
    )
    (net (code "104") (name "RESET") (class "Default")
      (node (ref "BOTTOM_HEADER1") (pin "1") (pinfunction "1_1") (pintype "passive"))
    )
    (net (code "105") (name "SCL_5V") (class "Default")
      (node (ref "Q4") (pin "3") (pinfunction "D_3") (pintype "bidirectional"))
      (node (ref "Q5") (pin "3") (pinfunction "D_3") (pintype "bidirectional"))
      (node (ref "R17") (pin "1") (pinfunction "1_1") (pintype "passive"))
      (node (ref "R7") (pin "1") (pinfunction "1_1") (pintype "passive"))
      (node (ref "U$1") (pin "19/A5/SCL") (pinfunction "19/A5/SCL_19/A5/SCL") (pintype "bidirectional"))
    )
    (net (code "106") (name "SDA_5V") (class "Default")
      (node (ref "Q3") (pin "3") (pinfunction "D_3") (pintype "bidirectional"))
      (node (ref "Q6") (pin "3") (pinfunction "D_3") (pintype "bidirectional"))
      (node (ref "R16") (pin "1") (pinfunction "1_1") (pintype "passive"))
      (node (ref "R6") (pin "2") (pinfunction "2_2") (pintype "passive"))
      (node (ref "U$1") (pin "18/A4/SDA") (pinfunction "18/A4/SDA_18/A4/SDA") (pintype "bidirectional"))
    )
    (net (code "107") (name "SW_MODE_SUPPLY") (class "Default")
      (node (ref "C2") (pin "+") (pinfunction "+_+") (pintype "passive"))
      (node (ref "C4") (pin "1") (pinfunction "1_1") (pintype "passive"))
      (node (ref "L1") (pin "2") (pinfunction "2_2") (pintype "passive"))
      (node (ref "MOTOR") (pin "2") (pinfunction "2_2") (pintype "passive"))
      (node (ref "R3") (pin "E") (pinfunction "E_E") (pintype "passive"))
    )
    (net (code "108") (name "VDD") (class "Default")
      (node (ref "C10") (pin "1") (pinfunction "P$1_1") (pintype "passive"))
      (node (ref "IC3") (pin "1") (pinfunction "VDDIO_1") (pintype "power_in"))
      (node (ref "IC3") (pin "22") (pinfunction "VDD_22") (pintype "power_in"))
      (node (ref "IC3") (pin "23") (pinfunction "VDD_23") (pintype "power_in"))
      (node (ref "IC3") (pin "3") (pinfunction "VDDIO_3") (pintype "power_in"))
      (node (ref "Q3") (pin "1") (pinfunction "G_1") (pintype "bidirectional"))
      (node (ref "Q4") (pin "1") (pinfunction "G_1") (pintype "bidirectional"))
      (node (ref "R14") (pin "2") (pinfunction "2_2") (pintype "passive"))
      (node (ref "R15") (pin "2") (pinfunction "2_2") (pintype "passive"))
      (node (ref "R18") (pin "2") (pinfunction "2_2") (pintype "passive"))
      (node (ref "R19") (pin "1") (pinfunction "1_1") (pintype "passive"))
      (node (ref "R20") (pin "1") (pinfunction "1_1") (pintype "passive"))
      (node (ref "R21") (pin "1") (pinfunction "1_1") (pintype "passive"))
      (node (ref "R22") (pin "1") (pinfunction "1_1") (pintype "passive"))
      (node (ref "U4") (pin "5") (pinfunction "OUT_5") (pintype "power_in"))
    )
    (net (code "109") (name "X_CHANNEL") (class "Default")
      (node (ref "ENCODER") (pin "2") (pinfunction "2_2") (pintype "passive"))
      (node (ref "R12") (pin "1") (pinfunction "1_1") (pintype "passive"))
    )
    (net (code "110") (name "X_CHANNEL_3V3") (class "Default")
      (node (ref "R12") (pin "2") (pinfunction "2_2") (pintype "passive"))
      (node (ref "R13") (pin "1") (pinfunction "1_1") (pintype "passive"))
      (node (ref "U$1") (pin "7") (pinfunction "7_7") (pintype "bidirectional"))
    )
    (net (code "111") (name "unconnected-(U$1-A21{slash}DAC0-Pad21{slash}DAC0)") (class "Default")
      (node (ref "U$1") (pin "21/DAC0") (pinfunction "A21/DAC0_21/DAC0") (pintype "bidirectional"))
    )
    (net (code "112") (name "unconnected-(U$1-Pad0{slash}RX)") (class "Default")
      (node (ref "U$1") (pin "0/RX") (pinfunction "0/RX_0/RX") (pintype "bidirectional"))
    )
    (net (code "113") (name "unconnected-(U$1-Pad1{slash}TX)") (class "Default")
      (node (ref "U$1") (pin "1/TX") (pinfunction "1/TX_1/TX") (pintype "bidirectional"))
    )
    (net (code "114") (name "unconnected-(U$1-Pad3V3)") (class "Default")
      (node (ref "U$1") (pin "3V3") (pinfunction "3V3_3V3") (pintype "bidirectional"))
    )
    (net (code "115") (name "unconnected-(U$1-Pad3V3_2)") (class "Default")
      (node (ref "U$1") (pin "3V3_2") (pinfunction "3V3_2_3V3_2") (pintype "bidirectional"))
    )
    (net (code "116") (name "unconnected-(U$1-Pad3V3_LO)") (class "Default")
      (node (ref "U$1") (pin "3V3_LO") (pinfunction "3V3_LO_3V3_LO") (pintype "bidirectional"))
    )
    (net (code "117") (name "unconnected-(U$1-Pad3{slash}CANTX)") (class "Default")
      (node (ref "U$1") (pin "3/CANTX") (pinfunction "3/CANTX_3/CANTX") (pintype "bidirectional"))
    )
    (net (code "118") (name "unconnected-(U$1-Pad8)") (class "Default")
      (node (ref "U$1") (pin "8") (pinfunction "8_8") (pintype "bidirectional"))
    )
    (net (code "119") (name "unconnected-(U$1-Pad9{slash}CS)") (class "Default")
      (node (ref "U$1") (pin "9/CS") (pinfunction "9/CS_9/CS") (pintype "bidirectional"))
    )
    (net (code "120") (name "unconnected-(U$1-Pad13{slash}SCK)") (class "Default")
      (node (ref "U$1") (pin "13/SCK") (pinfunction "13/SCK_13/SCK") (pintype "bidirectional"))
    )
    (net (code "121") (name "unconnected-(U$1-Pad14{slash}A0)") (class "Default")
      (node (ref "U$1") (pin "14/A0") (pinfunction "14/A0_14/A0") (pintype "bidirectional"))
    )
    (net (code "122") (name "unconnected-(U$1-Pad15{slash}A1)") (class "Default")
      (node (ref "U$1") (pin "15/A1") (pinfunction "15/A1_15/A1") (pintype "bidirectional"))
    )
    (net (code "123") (name "unconnected-(U$1-Pad16{slash}A2)") (class "Default")
      (node (ref "U$1") (pin "16/A2") (pinfunction "16/A2_16/A2") (pintype "bidirectional"))
    )
    (net (code "124") (name "unconnected-(U$1-Pad17{slash}A3)") (class "Default")
      (node (ref "U$1") (pin "17/A3") (pinfunction "17/A3_17/A3") (pintype "bidirectional"))
    )
    (net (code "125") (name "unconnected-(U$1-Pad20{slash}A6)") (class "Default")
      (node (ref "U$1") (pin "20/A6") (pinfunction "20/A6_20/A6") (pintype "bidirectional"))
    )
    (net (code "126") (name "unconnected-(U$1-Pad21{slash}A7)") (class "Default")
      (node (ref "U$1") (pin "21/A7") (pinfunction "21/A7_21/A7") (pintype "bidirectional"))
    )
    (net (code "127") (name "unconnected-(U$1-Pad22{slash}A8)") (class "Default")
      (node (ref "U$1") (pin "22/A8") (pinfunction "22/A8_22/A8") (pintype "bidirectional"))
    )
    (net (code "128") (name "unconnected-(U$1-Pad23{slash}A9)") (class "Default")
      (node (ref "U$1") (pin "23/A9") (pinfunction "23/A9_23/A9") (pintype "bidirectional"))
    )
    (net (code "129") (name "unconnected-(U$1-Pad24)") (class "Default")
      (node (ref "U$1") (pin "24") (pinfunction "24_24") (pintype "bidirectional"))
    )
    (net (code "130") (name "unconnected-(U$1-Pad25)") (class "Default")
      (node (ref "U$1") (pin "25") (pinfunction "25_25") (pintype "bidirectional"))
    )
    (net (code "131") (name "unconnected-(U$1-Pad26)") (class "Default")
      (node (ref "U$1") (pin "26") (pinfunction "26_26") (pintype "bidirectional"))
    )
    (net (code "132") (name "unconnected-(U$1-Pad28)") (class "Default")
      (node (ref "U$1") (pin "28") (pinfunction "28_28") (pintype "bidirectional"))
    )
    (net (code "133") (name "unconnected-(U$1-Pad29)") (class "Default")
      (node (ref "U$1") (pin "29") (pinfunction "29_29") (pintype "bidirectional"))
    )
    (net (code "134") (name "unconnected-(U$1-Pad30)") (class "Default")
      (node (ref "U$1") (pin "30") (pinfunction "30_30") (pintype "bidirectional"))
    )
    (net (code "135") (name "unconnected-(U$1-Pad31{slash}A12)") (class "Default")
      (node (ref "U$1") (pin "31/A12") (pinfunction "31/A12_31/A12") (pintype "bidirectional"))
    )
    (net (code "136") (name "unconnected-(U$1-Pad32{slash}A13)") (class "Default")
      (node (ref "U$1") (pin "32/A13") (pinfunction "32/A13_32/A13") (pintype "bidirectional"))
    )
    (net (code "137") (name "unconnected-(U$1-Pad33{slash}A14)") (class "Default")
      (node (ref "U$1") (pin "33/A14") (pinfunction "33/A14_33/A14") (pintype "bidirectional"))
    )
    (net (code "138") (name "unconnected-(U$1-Pad34{slash}A15)") (class "Default")
      (node (ref "U$1") (pin "34/A15") (pinfunction "34/A15_34/A15") (pintype "bidirectional"))
    )
    (net (code "139") (name "unconnected-(U$1-Pad35{slash}A16)") (class "Default")
      (node (ref "U$1") (pin "35/A16") (pinfunction "35/A16_35/A16") (pintype "bidirectional"))
    )
    (net (code "140") (name "unconnected-(U$1-Pad36{slash}A17)") (class "Default")
      (node (ref "U$1") (pin "36/A17") (pinfunction "36/A17_36/A17") (pintype "bidirectional"))
    )
    (net (code "141") (name "unconnected-(U$1-Pad37{slash}A18)") (class "Default")
      (node (ref "U$1") (pin "37/A18") (pinfunction "37/A18_37/A18") (pintype "bidirectional"))
    )
    (net (code "142") (name "unconnected-(U$1-Pad38{slash}A19)") (class "Default")
      (node (ref "U$1") (pin "38/A19") (pinfunction "38/A19_38/A19") (pintype "bidirectional"))
    )
    (net (code "143") (name "unconnected-(U$1-Pad39{slash}A20)") (class "Default")
      (node (ref "U$1") (pin "39/A20") (pinfunction "39/A20_39/A20") (pintype "bidirectional"))
    )
    (net (code "144") (name "unconnected-(U$1-PadA10)") (class "Default")
      (node (ref "U$1") (pin "A10") (pinfunction "A10_A10") (pintype "bidirectional"))
    )
    (net (code "145") (name "unconnected-(U$1-PadA11)") (class "Default")
      (node (ref "U$1") (pin "A11") (pinfunction "A11_A11") (pintype "bidirectional"))
    )
    (net (code "146") (name "unconnected-(U$1-PadA22{slash}DAC1)") (class "Default")
      (node (ref "U$1") (pin "A22/DAC1") (pinfunction "A22/DAC1_A22/DAC1") (pintype "bidirectional"))
    )
    (net (code "147") (name "unconnected-(U$1-PadAGND)") (class "Default")
      (node (ref "U$1") (pin "AGND") (pinfunction "AGND_AGND") (pintype "bidirectional"))
    )
    (net (code "148") (name "unconnected-(U$1-PadAREF)") (class "Default")
      (node (ref "U$1") (pin "AREF") (pinfunction "AREF_AREF") (pintype "bidirectional"))
    )
    (net (code "149") (name "unconnected-(U$1-PadGND2)") (class "Default")
      (node (ref "U$1") (pin "GND2") (pinfunction "GND2_GND2") (pintype "bidirectional"))
    )
    (net (code "150") (name "unconnected-(U$1-PadGND3)") (class "Default")
      (node (ref "U$1") (pin "GND3") (pinfunction "GND3_GND3") (pintype "bidirectional"))
    )
    (net (code "151") (name "unconnected-(U$1-PadPROG)") (class "Default")
      (node (ref "U$1") (pin "PROG") (pinfunction "PROG_PROG") (pintype "bidirectional"))
    )
    (net (code "152") (name "unconnected-(U$1-PadRESET)") (class "Default")
      (node (ref "U$1") (pin "RESET") (pinfunction "RESET_RESET") (pintype "bidirectional"))
    )
    (net (code "153") (name "unconnected-(U$1-PadU5V)") (class "Default")
      (node (ref "U$1") (pin "U5V") (pinfunction "U5V_U5V") (pintype "bidirectional"))
    )
    (net (code "154") (name "unconnected-(U$1-PadUD+)") (class "Default")
      (node (ref "U$1") (pin "UD+") (pinfunction "UD+_UD+") (pintype "bidirectional"))
    )
    (net (code "155") (name "unconnected-(U$1-PadUD-)") (class "Default")
      (node (ref "U$1") (pin "UD-") (pinfunction "UD-_UD-") (pintype "bidirectional"))
    )
    (net (code "156") (name "unconnected-(U$1-PadUGND1)") (class "Default")
      (node (ref "U$1") (pin "UGND1") (pinfunction "UGND1_UGND1") (pintype "bidirectional"))
    )
    (net (code "157") (name "unconnected-(U$1-PadUGND2)") (class "Default")
      (node (ref "U$1") (pin "UGND2") (pinfunction "UGND2_UGND2") (pintype "bidirectional"))
    )
    (net (code "158") (name "unconnected-(U$1-PadVBAT)") (class "Default")
      (node (ref "U$1") (pin "VBAT") (pinfunction "VBAT_VBAT") (pintype "bidirectional"))
    )
    (net (code "159") (name "unconnected-(U$1-PadVUSB)") (class "Default")
      (node (ref "U$1") (pin "VUSB") (pinfunction "VUSB_VUSB") (pintype "bidirectional"))
    )
    (net (code "160") (name "unconnected-(U4-P4-Pad4)") (class "Default")
      (node (ref "U4") (pin "4") (pinfunction "P4_4") (pintype "bidirectional"))
    )
    (net (code "161") (name "unconnected-(U5-P4-Pad4)") (class "Default")
      (node (ref "U5") (pin "4") (pinfunction "P4_4") (pintype "bidirectional"))
    )
  )
)
